# 05_-_L70.net
KiCad netlist of a schematic drawn in Altium Designer
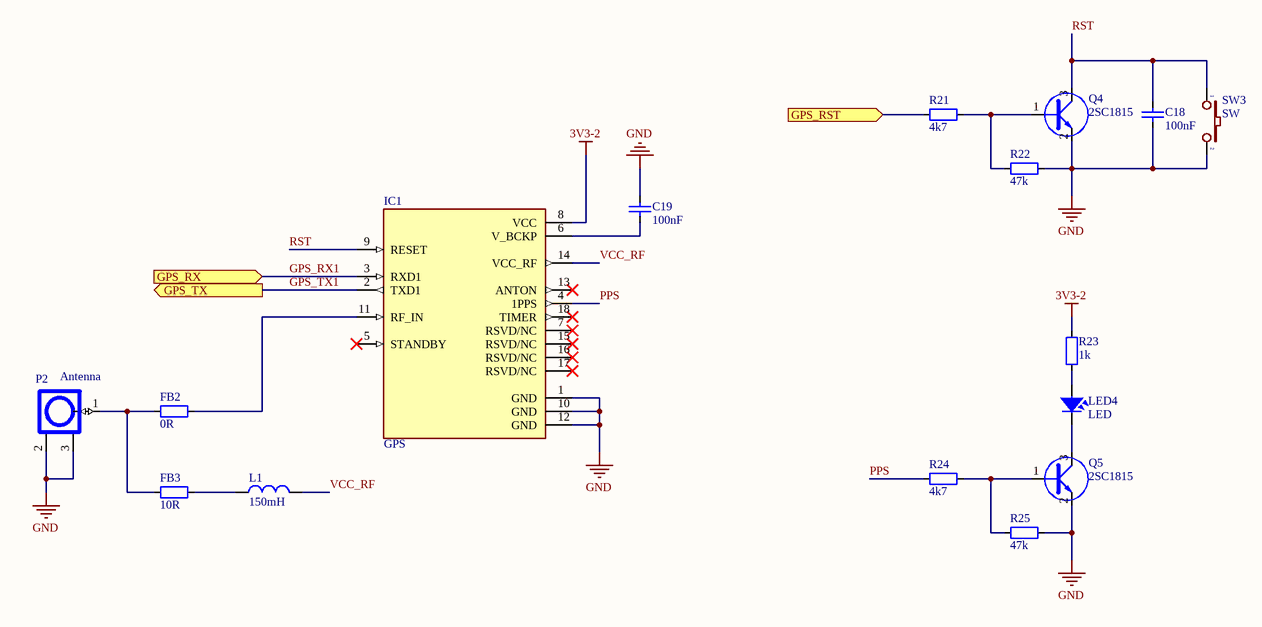
[diagram p0: [05] - L70.SchDoc]

(export (version "E")
  (design (tool "Eeschema 10.0.6"))
  (components
    (comp (ref "C18")
      (value "100nF")
      (footprint "CAP_0603")
      (description "Capacitor")
      (fields (field (name "PUBLISHER") "Altium Limited"))
      (libsource (lib "My Library") (part "CapSMD"))
    )
    (comp (ref "C19")
      (value "100nF")
      (footprint "CAP_0603")
      (description "Capacitor")
      (fields (field (name "PUBLISHER") "Altium Limited"))
      (libsource (lib "My Library") (part "CapSMD"))
    )
    (comp (ref "FB2")
      (value "0R")
      (footprint "RES-SMD-0603")
      (description "Resistor")
      (fields
        (field (name "MANUFACTURER") "Generic Components")
        (field (name "PUBLISHER") "Altium Hobart Technology Centre")
      )
      (libsource (lib "My Library") (part "Resistor - SMD"))
    )
    (comp (ref "FB3")
      (value "10R")
      (footprint "RES-SMD-0603")
      (description "Resistor")
      (fields
        (field (name "MANUFACTURER") "Generic Components")
        (field (name "PUBLISHER") "Altium Hobart Technology Centre")
      )
      (libsource (lib "My Library") (part "Resistor - SMD"))
    )
    (comp (ref "IC1")
      (value "GPS")
      (footprint "L70")
      (description "Quectel GPS IC")
      (libsource (lib "My Library") (part "L70"))
    )
    (comp (ref "L1")
      (value "150mH")
      (footprint "L-0603")
      (description "Inductor")
      (libsource (lib "My Library") (part "L1"))
    )
    (comp (ref "LED4")
      (value "LED")
      (footprint "LED-0805-Green")
      (description "LED Single colour Green and Red")
      (libsource (lib "My Library") (part "LED"))
    )
    (comp (ref "P2")
      (value "Antenna")
      (footprint "IPXS")
      (description "Antenna GSM GPS")
      (libsource (lib "My Library") (part "IPXSx66"))
    )
    (comp (ref "Q4")
      (value "2SC1815")
      (footprint "SOT23")
      (description "NPN 600mW, ECB")
      (libsource (lib "My Library") (part "2SC1815"))
    )
    (comp (ref "Q5")
      (value "2SC1815")
      (footprint "SOT23")
      (description "NPN 600mW, ECB")
      (libsource (lib "My Library") (part "2SC1815"))
    )
    (comp (ref "R21")
      (value "4k7")
      (footprint "RES-SMD-0603")
      (description "Resistor")
      (fields
        (field (name "MANUFACTURER") "Generic Components")
        (field (name "PUBLISHER") "Altium Hobart Technology Centre")
      )
      (libsource (lib "My Library") (part "Resistor - SMD"))
    )
    (comp (ref "R22")
      (value "47k")
      (footprint "RES-SMD-0603")
      (description "Resistor")
      (fields
        (field (name "MANUFACTURER") "Generic Components")
        (field (name "PUBLISHER") "Altium Hobart Technology Centre")
      )
      (libsource (lib "My Library") (part "Resistor - SMD"))
    )
    (comp (ref "R23")
      (value "1k")
      (footprint "RES-SMD-0603")
      (description "Resistor")
      (fields
        (field (name "MANUFACTURER") "Generic Components")
        (field (name "PUBLISHER") "Altium Hobart Technology Centre")
      )
      (libsource (lib "My Library") (part "Resistor - SMD"))
    )
    (comp (ref "R24")
      (value "4k7")
      (footprint "RES-SMD-0603")
      (description "Resistor")
      (fields
        (field (name "MANUFACTURER") "Generic Components")
        (field (name "PUBLISHER") "Altium Hobart Technology Centre")
      )
      (libsource (lib "My Library") (part "Resistor - SMD"))
    )
    (comp (ref "R25")
      (value "47k")
      (footprint "RES-SMD-0603")
      (description "Resistor")
      (fields
        (field (name "MANUFACTURER") "Generic Components")
        (field (name "PUBLISHER") "Altium Hobart Technology Centre")
      )
      (libsource (lib "My Library") (part "Resistor - SMD"))
    )
    (comp (ref "SW3")
      (value "SW")
      (footprint "SW2")
      (description "Switch button 2 pin")
      (libsource (lib "My Library") (part "SW2"))
    )
  )
  (nets
    (net (code "1") (name "/GPS_RST") (class "Default")
      (node (ref "R21") (pin "1") (pinfunction "1_1") (pintype "passive"))
    )
    (net (code "2") (name "/GPS_RX1") (class "Default")
      (node (ref "IC1") (pin "3") (pinfunction "RXD1_3") (pintype "input"))
    )
    (net (code "3") (name "/GPS_TX1") (class "Default")
      (node (ref "IC1") (pin "2") (pinfunction "TXD1_2") (pintype "output"))
    )
    (net (code "4") (name "/PPS") (class "Default")
      (node (ref "IC1") (pin "4") (pinfunction "1PPS_4") (pintype "output"))
      (node (ref "R24") (pin "1") (pinfunction "1_1") (pintype "passive"))
    )
    (net (code "5") (name "/RST") (class "Default")
      (node (ref "C18") (pin "2") (pinfunction "2_2") (pintype "passive"))
      (node (ref "IC1") (pin "9") (pinfunction "RESET_9") (pintype "input"))
      (node (ref "Q4") (pin "3") (pinfunction "C_3") (pintype "passive"))
      (node (ref "SW3") (pin "1") (pinfunction "1_1") (pintype "passive"))
    )
    (net (code "6") (name "/VCC_RF") (class "Default")
      (node (ref "IC1") (pin "14") (pinfunction "VCC_RF_14") (pintype "output"))
      (node (ref "L1") (pin "2") (pinfunction "2_2") (pintype "passive"))
    )
    (net (code "7") (name "3V3-2") (class "Default")
      (node (ref "IC1") (pin "8") (pinfunction "VCC_8") (pintype "power_in"))
      (node (ref "R23") (pin "2") (pinfunction "2_2") (pintype "passive"))
    )
    (net (code "8") (name "GND") (class "Default")
      (node (ref "C18") (pin "1") (pinfunction "1_1") (pintype "passive"))
      (node (ref "C19") (pin "1") (pinfunction "1_1") (pintype "passive"))
      (node (ref "IC1") (pin "1") (pinfunction "GND_1") (pintype "power_in"))
      (node (ref "IC1") (pin "10") (pinfunction "GND_10") (pintype "power_in"))
      (node (ref "IC1") (pin "12") (pinfunction "GND_12") (pintype "power_in"))
      (node (ref "P2") (pin "2") (pintype "passive"))
      (node (ref "P2") (pin "3") (pintype "passive"))
      (node (ref "Q4") (pin "2") (pinfunction "E_2") (pintype "passive"))
      (node (ref "Q5") (pin "2") (pinfunction "E_2") (pintype "passive"))
      (node (ref "R22") (pin "2") (pinfunction "2_2") (pintype "passive"))
      (node (ref "R25") (pin "2") (pinfunction "2_2") (pintype "passive"))
      (node (ref "SW3") (pin "2") (pinfunction "2_2") (pintype "passive"))
    )
    (net (code "9") (name "Net-(FB2-Pad1)") (class "Default")
      (node (ref "FB2") (pin "1") (pinfunction "1_1") (pintype "passive"))
      (node (ref "FB3") (pin "1") (pinfunction "1_1") (pintype "passive"))
      (node (ref "P2") (pin "1") (pintype "bidirectional"))
    )
    (net (code "10") (name "Net-(FB3-Pad2)") (class "Default")
      (node (ref "FB3") (pin "2") (pinfunction "2_2") (pintype "passive"))
      (node (ref "L1") (pin "1") (pinfunction "1_1") (pintype "passive"))
    )
    (net (code "11") (name "Net-(IC1-RF_IN)") (class "Default")
      (node (ref "FB2") (pin "2") (pinfunction "2_2") (pintype "passive"))
      (node (ref "IC1") (pin "11") (pinfunction "RF_IN_11") (pintype "input"))
    )
    (net (code "12") (name "Net-(IC1-V_BCKP)") (class "Default")
      (node (ref "C19") (pin "2") (pinfunction "2_2") (pintype "passive"))
      (node (ref "IC1") (pin "6") (pinfunction "V_BCKP_6") (pintype "power_in"))
    )
    (net (code "13") (name "Net-(LED4-Pad1)") (class "Default")
      (node (ref "LED4") (pin "1") (pinfunction "1_1") (pintype "passive"))
      (node (ref "R23") (pin "1") (pinfunction "1_1") (pintype "passive"))
    )
    (net (code "14") (name "Net-(Q4-B)") (class "Default")
      (node (ref "Q4") (pin "1") (pinfunction "B_1") (pintype "passive"))
      (node (ref "R21") (pin "2") (pinfunction "2_2") (pintype "passive"))
      (node (ref "R22") (pin "1") (pinfunction "1_1") (pintype "passive"))
    )
    (net (code "15") (name "Net-(Q5-B)") (class "Default")
      (node (ref "Q5") (pin "1") (pinfunction "B_1") (pintype "passive"))
      (node (ref "R24") (pin "2") (pinfunction "2_2") (pintype "passive"))
      (node (ref "R25") (pin "1") (pinfunction "1_1") (pintype "passive"))
    )
    (net (code "16") (name "Net-(Q5-C)") (class "Default")
      (node (ref "LED4") (pin "2") (pinfunction "2_2") (pintype "passive"))
      (node (ref "Q5") (pin "3") (pinfunction "C_3") (pintype "passive"))
    )
    (net (code "17") (name "unconnected-(IC1-ANTON-Pad13)") (class "Default")
      (node (ref "IC1") (pin "13") (pinfunction "ANTON_13") (pintype "output+no_connect"))
    )
    (net (code "18") (name "unconnected-(IC1-RSVD{slash}NC-Pad7)") (class "Default")
      (node (ref "IC1") (pin "7") (pinfunction "RSVD/NC_7") (pintype "passive+no_connect"))
    )
    (net (code "19") (name "unconnected-(IC1-RSVD{slash}NC-Pad15)") (class "Default")
      (node (ref "IC1") (pin "15") (pinfunction "RSVD/NC_15") (pintype "passive+no_connect"))
    )
    (net (code "20") (name "unconnected-(IC1-RSVD{slash}NC-Pad16)") (class "Default")
      (node (ref "IC1") (pin "16") (pinfunction "RSVD/NC_16") (pintype "passive+no_connect"))
    )
    (net (code "21") (name "unconnected-(IC1-RSVD{slash}NC-Pad17)") (class "Default")
      (node (ref "IC1") (pin "17") (pinfunction "RSVD/NC_17") (pintype "passive+no_connect"))
    )
    (net (code "22") (name "unconnected-(IC1-STANDBY-Pad5)") (class "Default")
      (node (ref "IC1") (pin "5") (pinfunction "STANDBY_5") (pintype "input+no_connect"))
    )
    (net (code "23") (name "unconnected-(IC1-TIMER-Pad18)") (class "Default")
      (node (ref "IC1") (pin "18") (pinfunction "TIMER_18") (pintype "output+no_connect"))
    )
  )
)
